# Ikea_Molgan.net
KiCad netlist of a schematic drawn in EAGLE
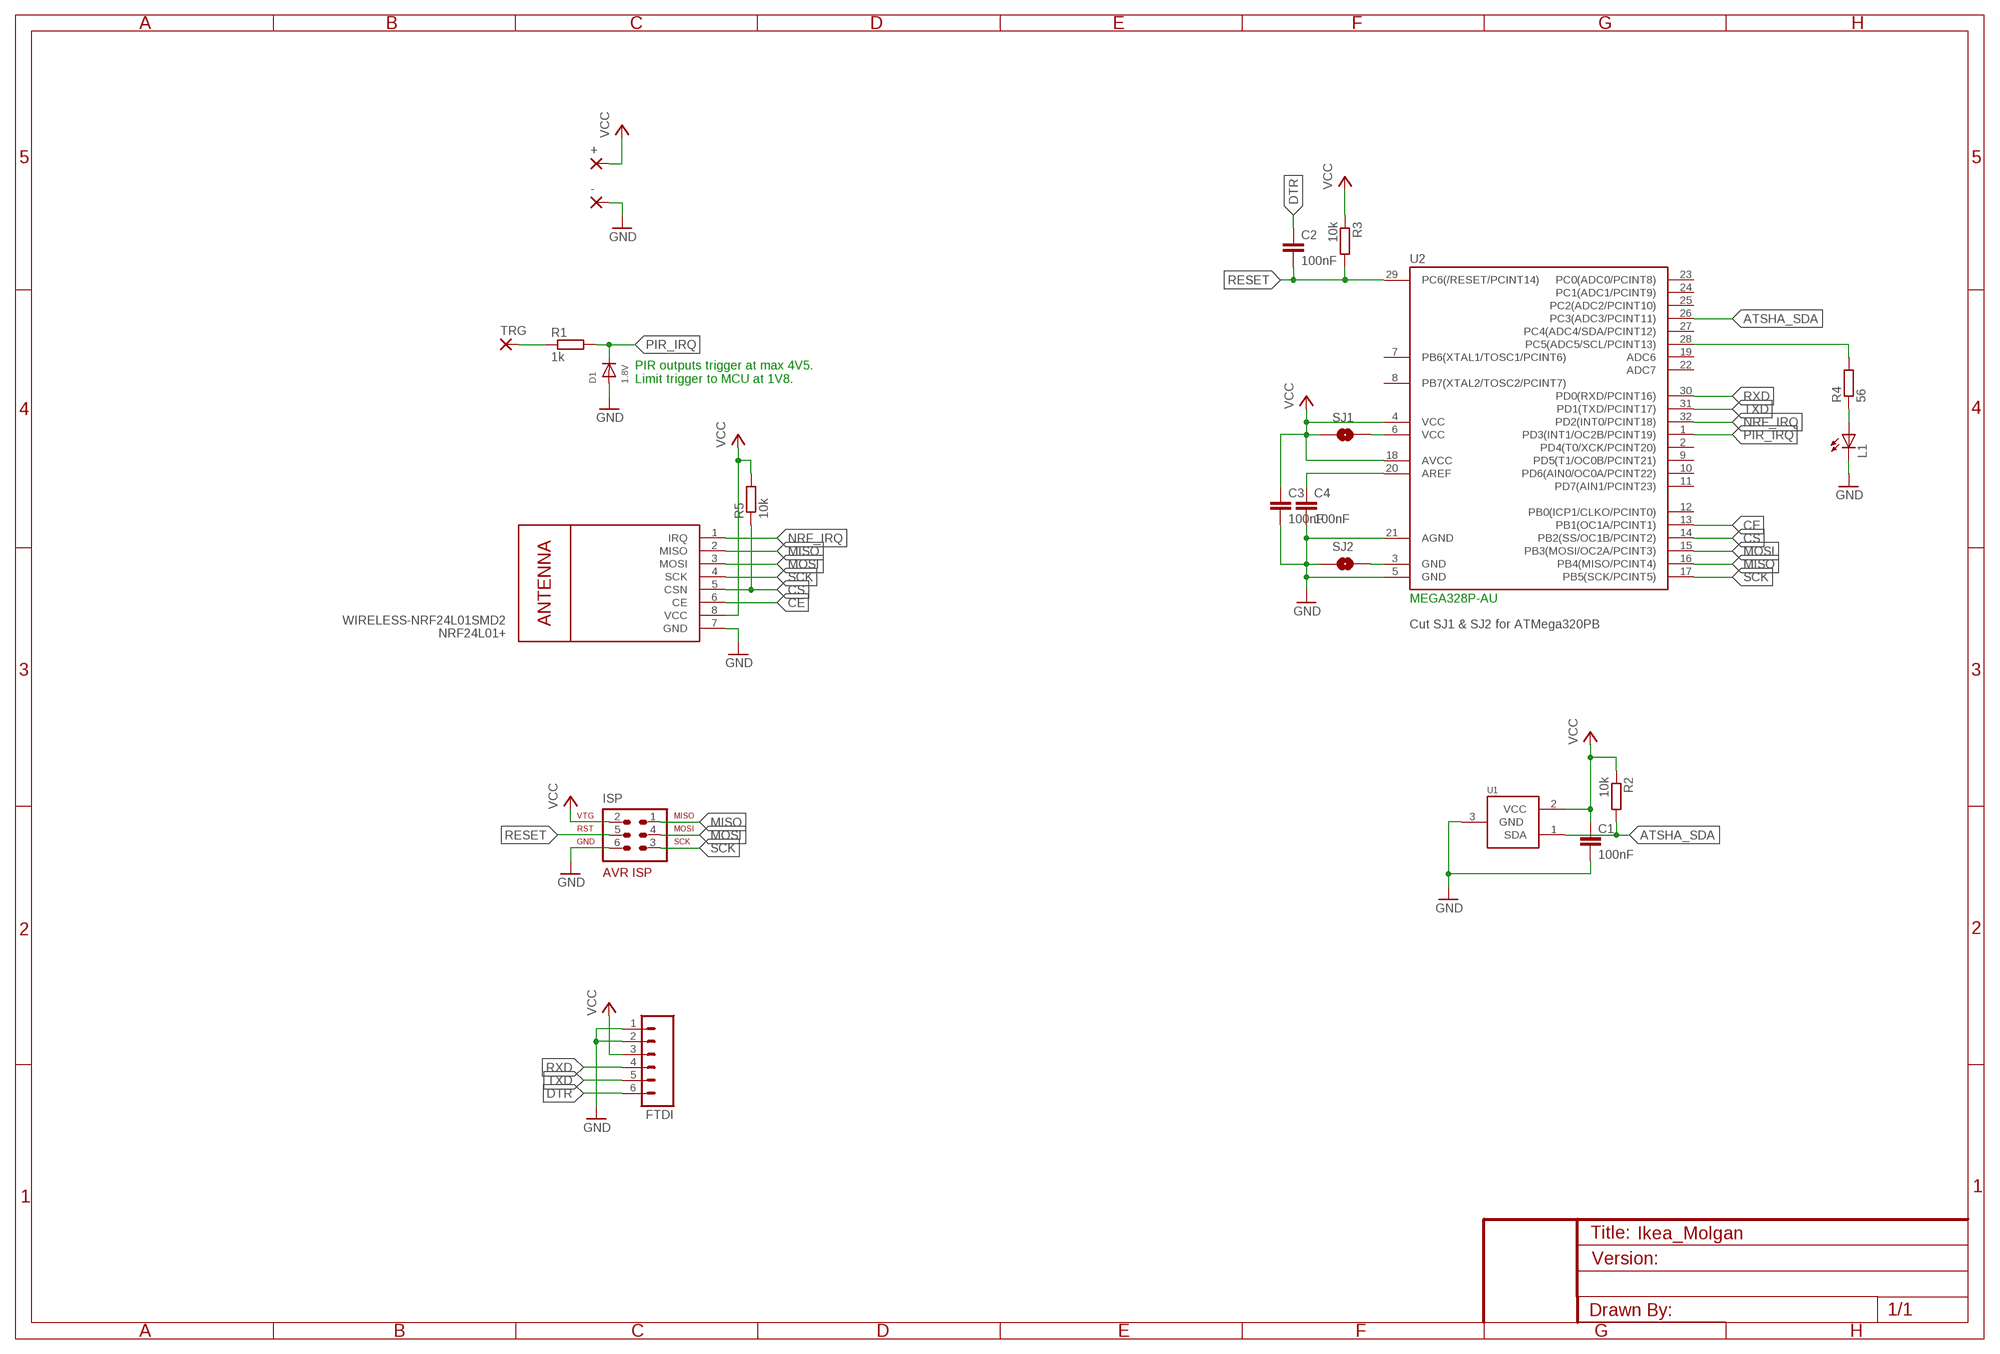
[diagram p0: schematic, sheet 1]

(export (version "E")
  (design (tool "Eeschema 10.0.6"))
  (components
    (comp (ref "+")
      (value "WIREPADSMD2,54-5,08")
      (footprint "eagle-import:SMD2,54-5,08")
      (libsource (lib "eagle-import") (part "WIREPADSMD2,54-5,08"))
    )
    (comp (ref "-")
      (value "WIREPADSMD2,54-5,08")
      (footprint "eagle-import:SMD2,54-5,08")
      (libsource (lib "eagle-import") (part "WIREPADSMD2,54-5,08"))
    )
    (comp (ref "C1")
      (value "100nF")
      (footprint "eagle-import:C0805")
      (libsource (lib "eagle-import") (part "C-EUC0805"))
    )
    (comp (ref "C2")
      (value "100nF")
      (footprint "eagle-import:C0805")
      (libsource (lib "eagle-import") (part "C-EUC0805"))
    )
    (comp (ref "C3")
      (value "100nF")
      (footprint "eagle-import:C0805")
      (libsource (lib "eagle-import") (part "C-EUC0805"))
    )
    (comp (ref "C4")
      (value "100nF")
      (footprint "eagle-import:C0805")
      (libsource (lib "eagle-import") (part "C-EUC0805"))
    )
    (comp (ref "D1")
      (value "1.8V")
      (footprint "eagle-import:SOD-123")
      (libsource (lib "eagle-import") (part "DIODESOD-123"))
    )
    (comp (ref "FTDI")
      (value "M06SIP")
      (footprint "eagle-import:1X06")
      (libsource (lib "eagle-import") (part "M06SIP"))
    )
    (comp (ref "ISP")
      (value "AVR-ISP-6")
      (footprint "eagle-import:AVR-ISP-6")
      (libsource (lib "eagle-import") (part "AVR-ISP-6"))
    )
    (comp (ref "L1")
      (value "LEDCHIPLED_0805")
      (footprint "eagle-import:CHIPLED_0805")
      (libsource (lib "eagle-import") (part "LEDCHIPLED_0805"))
    )
    (comp (ref "NRF24L01+")
      (value "WIRELESS-NRF24L01SMD2")
      (footprint "eagle-import:WIRELESS-NRF24L01-SMD-2")
      (libsource (lib "eagle-import") (part "WIRELESS-NRF24L01SMD2"))
    )
    (comp (ref "R1")
      (value "1k")
      (footprint "eagle-import:R0805")
      (libsource (lib "eagle-import") (part "R-EU_R0805"))
    )
    (comp (ref "R2")
      (value "10k")
      (footprint "eagle-import:R0805")
      (libsource (lib "eagle-import") (part "R-EU_R0805"))
    )
    (comp (ref "R3")
      (value "10k")
      (footprint "eagle-import:R0805")
      (libsource (lib "eagle-import") (part "R-EU_R0805"))
    )
    (comp (ref "R4")
      (value "56")
      (footprint "eagle-import:R0805")
      (libsource (lib "eagle-import") (part "R-EU_R0805"))
    )
    (comp (ref "R5")
      (value "10k")
      (footprint "eagle-import:R0805")
      (libsource (lib "eagle-import") (part "R-EU_R0805"))
    )
    (comp (ref "SJ1")
      (value "SOLDERJUMPERTRACE")
      (footprint "eagle-import:SJ_2S-TRACE")
      (libsource (lib "eagle-import") (part "SOLDERJUMPERTRACE"))
    )
    (comp (ref "SJ2")
      (value "SOLDERJUMPERTRACE")
      (footprint "eagle-import:SJ_2S-TRACE")
      (libsource (lib "eagle-import") (part "SOLDERJUMPERTRACE"))
    )
    (comp (ref "TRG")
      (value "WIREPADSMD2,54-5,08")
      (footprint "eagle-import:SMD2,54-5,08")
      (libsource (lib "eagle-import") (part "WIREPADSMD2,54-5,08"))
    )
    (comp (ref "U1")
      (value "IC_ATSHA204A_CRYPT")
      (footprint "eagle-import:SOT23-3")
      (libsource (lib "eagle-import") (part "IC_ATSHA204A_CRYPT"))
    )
    (comp (ref "U2")
      (value "MEGA328P-AU")
      (footprint "eagle-import:TQFP32-08")
      (libsource (lib "eagle-import") (part "MEGA48/88/168-AU"))
    )
  )
  (nets
    (net (code "1") (name "ATSHA_SDA") (class "Default")
      (node (ref "R2") (pin "2") (pinfunction "2_2") (pintype "passive"))
      (node (ref "U1") (pin "1") (pinfunction "SDA_1") (pintype "bidirectional"))
      (node (ref "U2") (pin "26") (pinfunction "PC3(ADC3/PCINT11)_26") (pintype "bidirectional"))
    )
    (net (code "2") (name "CE") (class "Default")
      (node (ref "NRF24L01+") (pin "6") (pinfunction "CE_6") (pintype "bidirectional"))
      (node (ref "U2") (pin "13") (pinfunction "PB1(OC1A/PCINT1)_13") (pintype "bidirectional"))
    )
    (net (code "3") (name "CS") (class "Default")
      (node (ref "NRF24L01+") (pin "5") (pinfunction "CSN_5") (pintype "bidirectional"))
      (node (ref "R5") (pin "1") (pinfunction "1_1") (pintype "passive"))
      (node (ref "U2") (pin "14") (pinfunction "PB2(SS/OC1B/PCINT2)_14") (pintype "bidirectional"))
    )
    (net (code "4") (name "DTR") (class "Default")
      (node (ref "C2") (pin "1") (pinfunction "1_1") (pintype "passive"))
      (node (ref "FTDI") (pin "6") (pinfunction "6_6") (pintype "passive"))
    )
    (net (code "5") (name "GND") (class "Default")
      (node (ref "-") (pin "1") (pinfunction "P_1") (pintype "passive"))
      (node (ref "C1") (pin "2") (pinfunction "2_2") (pintype "passive"))
      (node (ref "C3") (pin "2") (pinfunction "2_2") (pintype "passive"))
      (node (ref "C4") (pin "2") (pinfunction "2_2") (pintype "passive"))
      (node (ref "D1") (pin "A") (pinfunction "A_A") (pintype "passive"))
      (node (ref "FTDI") (pin "1") (pinfunction "1_1") (pintype "passive"))
      (node (ref "FTDI") (pin "2") (pinfunction "2_2") (pintype "passive"))
      (node (ref "ISP") (pin "6") (pinfunction "6_6") (pintype "passive"))
      (node (ref "L1") (pin "C") (pinfunction "C_C") (pintype "passive"))
      (node (ref "NRF24L01+") (pin "7") (pinfunction "GND_7") (pintype "power_in"))
      (node (ref "SJ2") (pin "1") (pinfunction "1_1") (pintype "passive"))
      (node (ref "U1") (pin "3") (pinfunction "GND_3") (pintype "bidirectional"))
      (node (ref "U2") (pin "21") (pinfunction "AGND_21") (pintype "power_in"))
      (node (ref "U2") (pin "5") (pinfunction "GND_5") (pintype "power_in"))
    )
    (net (code "6") (name "MISO") (class "Default")
      (node (ref "ISP") (pin "1") (pinfunction "1_1") (pintype "passive"))
      (node (ref "NRF24L01+") (pin "2") (pinfunction "MISO_2") (pintype "bidirectional"))
      (node (ref "U2") (pin "16") (pinfunction "PB4(MISO/PCINT4)_16") (pintype "bidirectional"))
    )
    (net (code "7") (name "MOSI") (class "Default")
      (node (ref "ISP") (pin "4") (pinfunction "4_4") (pintype "passive"))
      (node (ref "NRF24L01+") (pin "3") (pinfunction "MOSI_3") (pintype "bidirectional"))
      (node (ref "U2") (pin "15") (pinfunction "PB3(MOSI/OC2A/PCINT3)_15") (pintype "bidirectional"))
    )
    (net (code "8") (name "NRF_IRQ") (class "Default")
      (node (ref "NRF24L01+") (pin "1") (pinfunction "IRQ_1") (pintype "bidirectional"))
      (node (ref "U2") (pin "32") (pinfunction "PD2(INT0/PCINT18)_32") (pintype "bidirectional"))
    )
    (net (code "9") (name "Net-(L1-PadA)") (class "Default")
      (node (ref "L1") (pin "A") (pinfunction "A_A") (pintype "passive"))
      (node (ref "R4") (pin "1") (pinfunction "1_1") (pintype "passive"))
    )
    (net (code "10") (name "Net-(SJ1-Pad2)") (class "Default")
      (node (ref "SJ1") (pin "2") (pinfunction "2_2") (pintype "passive"))
      (node (ref "U2") (pin "6") (pinfunction "VCC_6") (pintype "power_in"))
    )
    (net (code "11") (name "Net-(SJ2-Pad2)") (class "Default")
      (node (ref "SJ2") (pin "2") (pinfunction "2_2") (pintype "passive"))
      (node (ref "U2") (pin "3") (pinfunction "GND_3") (pintype "power_in"))
    )
    (net (code "12") (name "Net-(TRG-P)") (class "Default")
      (node (ref "R1") (pin "1") (pinfunction "1_1") (pintype "passive"))
      (node (ref "TRG") (pin "1") (pinfunction "P_1") (pintype "passive"))
    )
    (net (code "13") (name "Net-(U2-AREF)") (class "Default")
      (node (ref "C4") (pin "1") (pinfunction "1_1") (pintype "passive"))
      (node (ref "U2") (pin "20") (pinfunction "AREF_20") (pintype "passive"))
    )
    (net (code "14") (name "Net-(U2-PC5(ADC5{slash}SCL{slash}PCINT13))") (class "Default")
      (node (ref "R4") (pin "2") (pinfunction "2_2") (pintype "passive"))
      (node (ref "U2") (pin "28") (pinfunction "PC5(ADC5/SCL/PCINT13)_28") (pintype "bidirectional"))
    )
    (net (code "15") (name "PIR_IRQ") (class "Default")
      (node (ref "D1") (pin "C") (pinfunction "C_C") (pintype "passive"))
      (node (ref "R1") (pin "2") (pinfunction "2_2") (pintype "passive"))
      (node (ref "U2") (pin "1") (pinfunction "PD3(INT1/OC2B/PCINT19)_1") (pintype "bidirectional"))
    )
    (net (code "16") (name "RESET") (class "Default")
      (node (ref "C2") (pin "2") (pinfunction "2_2") (pintype "passive"))
      (node (ref "ISP") (pin "5") (pinfunction "5_5") (pintype "passive"))
      (node (ref "R3") (pin "2") (pinfunction "2_2") (pintype "passive"))
      (node (ref "U2") (pin "29") (pinfunction "PC6(/RESET/PCINT14)_29") (pintype "bidirectional"))
    )
    (net (code "17") (name "RXD") (class "Default")
      (node (ref "FTDI") (pin "4") (pinfunction "4_4") (pintype "passive"))
      (node (ref "U2") (pin "30") (pinfunction "PD0(RXD/PCINT16)_30") (pintype "bidirectional"))
    )
    (net (code "18") (name "SCK") (class "Default")
      (node (ref "ISP") (pin "3") (pinfunction "3_3") (pintype "passive"))
      (node (ref "NRF24L01+") (pin "4") (pinfunction "SCK_4") (pintype "bidirectional"))
      (node (ref "U2") (pin "17") (pinfunction "PB5(SCK/PCINT5)_17") (pintype "bidirectional"))
    )
    (net (code "19") (name "TXD") (class "Default")
      (node (ref "FTDI") (pin "5") (pinfunction "5_5") (pintype "passive"))
      (node (ref "U2") (pin "31") (pinfunction "PD1(TXD/PCINT17)_31") (pintype "bidirectional"))
    )
    (net (code "20") (name "VCC") (class "Default")
      (node (ref "+") (pin "1") (pinfunction "P_1") (pintype "passive"))
      (node (ref "C1") (pin "1") (pinfunction "1_1") (pintype "passive"))
      (node (ref "C3") (pin "1") (pinfunction "1_1") (pintype "passive"))
      (node (ref "FTDI") (pin "3") (pinfunction "3_3") (pintype "passive"))
      (node (ref "ISP") (pin "2") (pinfunction "2_2") (pintype "passive"))
      (node (ref "NRF24L01+") (pin "8") (pinfunction "VCC_8") (pintype "power_in"))
      (node (ref "R2") (pin "1") (pinfunction "1_1") (pintype "passive"))
      (node (ref "R3") (pin "1") (pinfunction "1_1") (pintype "passive"))
      (node (ref "R5") (pin "2") (pinfunction "2_2") (pintype "passive"))
      (node (ref "SJ1") (pin "1") (pinfunction "1_1") (pintype "passive"))
      (node (ref "U1") (pin "2") (pinfunction "VCC_2") (pintype "bidirectional"))
      (node (ref "U2") (pin "18") (pinfunction "AVCC_18") (pintype "passive"))
      (node (ref "U2") (pin "4") (pinfunction "VCC_4") (pintype "power_in"))
    )
    (net (code "21") (name "unconnected-(U2-ADC6-Pad19)") (class "Default")
      (node (ref "U2") (pin "19") (pinfunction "ADC6_19") (pintype "passive"))
    )
    (net (code "22") (name "unconnected-(U2-ADC7-Pad22)") (class "Default")
      (node (ref "U2") (pin "22") (pinfunction "ADC7_22") (pintype "passive"))
    )
    (net (code "23") (name "unconnected-(U2-PB0(ICP1{slash}CLKO{slash}PCINT0)-Pad12)") (class "Default")
      (node (ref "U2") (pin "12") (pinfunction "PB0(ICP1/CLKO/PCINT0)_12") (pintype "bidirectional"))
    )
    (net (code "24") (name "unconnected-(U2-PB6(XTAL1{slash}TOSC1{slash}PCINT6)-Pad7)") (class "Default")
      (node (ref "U2") (pin "7") (pinfunction "PB6(XTAL1/TOSC1/PCINT6)_7") (pintype "bidirectional"))
    )
    (net (code "25") (name "unconnected-(U2-PB7(XTAL2{slash}TOSC2{slash}PCINT7)-Pad8)") (class "Default")
      (node (ref "U2") (pin "8") (pinfunction "PB7(XTAL2/TOSC2/PCINT7)_8") (pintype "bidirectional"))
    )
    (net (code "26") (name "unconnected-(U2-PC0(ADC0{slash}PCINT8)-Pad23)") (class "Default")
      (node (ref "U2") (pin "23") (pinfunction "PC0(ADC0/PCINT8)_23") (pintype "bidirectional"))
    )
    (net (code "27") (name "unconnected-(U2-PC1(ADC1{slash}PCINT9)-Pad24)") (class "Default")
      (node (ref "U2") (pin "24") (pinfunction "PC1(ADC1/PCINT9)_24") (pintype "bidirectional"))
    )
    (net (code "28") (name "unconnected-(U2-PC2(ADC2{slash}PCINT10)-Pad25)") (class "Default")
      (node (ref "U2") (pin "25") (pinfunction "PC2(ADC2/PCINT10)_25") (pintype "bidirectional"))
    )
    (net (code "29") (name "unconnected-(U2-PC4(ADC4{slash}SDA{slash}PCINT12)-Pad27)") (class "Default")
      (node (ref "U2") (pin "27") (pinfunction "PC4(ADC4/SDA/PCINT12)_27") (pintype "bidirectional"))
    )
    (net (code "30") (name "unconnected-(U2-PD4(T0{slash}XCK{slash}PCINT20)-Pad2)") (class "Default")
      (node (ref "U2") (pin "2") (pinfunction "PD4(T0/XCK/PCINT20)_2") (pintype "bidirectional"))
    )
    (net (code "31") (name "unconnected-(U2-PD5(T1{slash}OC0B{slash}PCINT21)-Pad9)") (class "Default")
      (node (ref "U2") (pin "9") (pinfunction "PD5(T1/OC0B/PCINT21)_9") (pintype "bidirectional"))
    )
    (net (code "32") (name "unconnected-(U2-PD6(AIN0{slash}OC0A{slash}PCINT22)-Pad10)") (class "Default")
      (node (ref "U2") (pin "10") (pinfunction "PD6(AIN0/OC0A/PCINT22)_10") (pintype "bidirectional"))
    )
    (net (code "33") (name "unconnected-(U2-PD7(AIN1{slash}PCINT23)-Pad11)") (class "Default")
      (node (ref "U2") (pin "11") (pinfunction "PD7(AIN1/PCINT23)_11") (pintype "bidirectional"))
    )
  )
)
